# separation.net
KiCad netlist of a schematic drawn in EAGLE
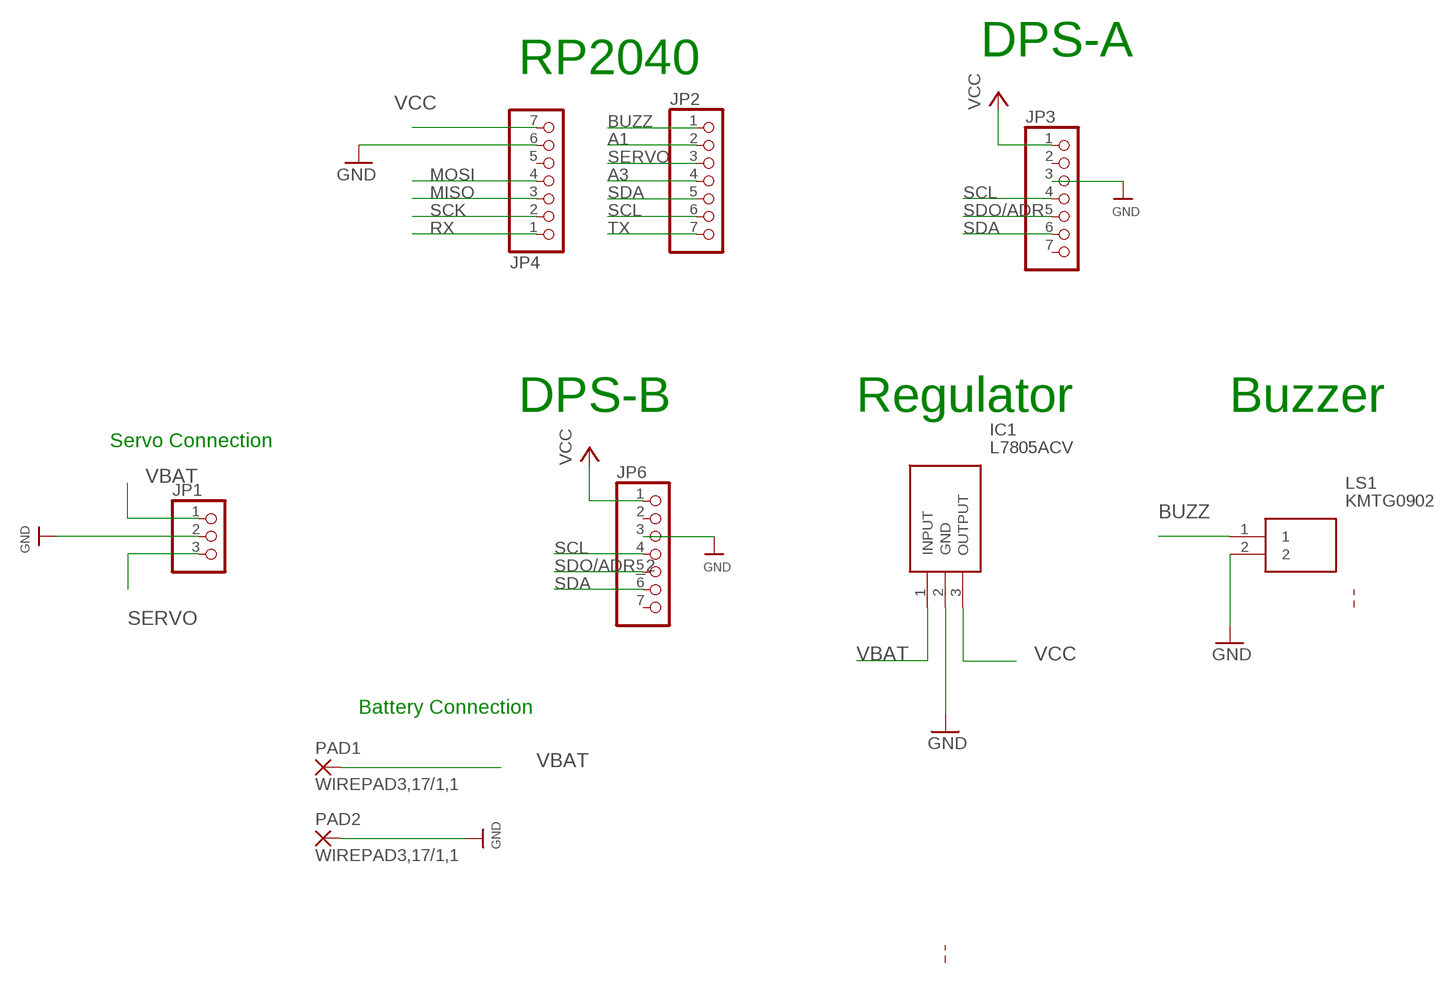
[diagram p0: schematic, sheet 1]

(export (version "E")
  (design (tool "Eeschema 10.0.6"))
  (components
    (comp (ref "IC1")
      (value "L7805ACV")
      (footprint "eagle-import:TO255P460X1020X2008-3P")
      (fields (field (name "RS_PART_NUMBER") "2988508P"))
      (libsource (lib "eagle-import") (part "L7805ACV"))
    )
    (comp (ref "JP1")
      (value "PINHD-1X3")
      (footprint "eagle-import:1X03")
      (libsource (lib "eagle-import") (part "PINHD-1X3"))
    )
    (comp (ref "JP2")
      (value "HEADER-1X7")
      (footprint "eagle-import:1X07_OVAL")
      (libsource (lib "eagle-import") (part "HEADER-1X7"))
    )
    (comp (ref "JP3")
      (value "HEADER-1X770MIL")
      (footprint "eagle-import:1X07_ROUND_70")
      (libsource (lib "eagle-import") (part "HEADER-1X770MIL"))
    )
    (comp (ref "JP4")
      (value "HEADER-1X7")
      (footprint "eagle-import:1X07_OVAL")
      (libsource (lib "eagle-import") (part "HEADER-1X7"))
    )
    (comp (ref "JP6")
      (value "HEADER-1X770MIL")
      (footprint "eagle-import:1X07_ROUND_70")
      (libsource (lib "eagle-import") (part "HEADER-1X770MIL"))
    )
    (comp (ref "LS1")
      (value "KMTG0902")
      (footprint "eagle-import:KMTG0902")
      (fields (field (name "RS_PART_NUMBER") "1812715"))
      (libsource (lib "eagle-import") (part "KMTG0902"))
    )
    (comp (ref "PAD1")
      (value "WIREPAD3,17/1,1")
      (footprint "eagle-import:3,17_1,1")
      (libsource (lib "eagle-import") (part "WIREPAD3,17/1,1"))
    )
    (comp (ref "PAD2")
      (value "WIREPAD3,17/1,1")
      (footprint "eagle-import:3,17_1,1")
      (libsource (lib "eagle-import") (part "WIREPAD3,17/1,1"))
    )
  )
  (nets
    (net (code "1") (name "/A1") (class "Default")
      (node (ref "JP2") (pin "2") (pinfunction "2_2") (pintype "passive"))
    )
    (net (code "2") (name "/A3") (class "Default")
      (node (ref "JP2") (pin "4") (pinfunction "4_4") (pintype "passive"))
    )
    (net (code "3") (name "/BUZZ") (class "Default")
      (node (ref "JP2") (pin "1") (pinfunction "1_1") (pintype "passive"))
      (node (ref "LS1") (pin "1") (pinfunction "1_1") (pintype "bidirectional"))
    )
    (net (code "4") (name "/MISO") (class "Default")
      (node (ref "JP4") (pin "3") (pinfunction "3_3") (pintype "passive"))
    )
    (net (code "5") (name "/MOSI") (class "Default")
      (node (ref "JP4") (pin "4") (pinfunction "4_4") (pintype "passive"))
    )
    (net (code "6") (name "/RX") (class "Default")
      (node (ref "JP4") (pin "1") (pinfunction "1_1") (pintype "passive"))
    )
    (net (code "7") (name "/SCK") (class "Default")
      (node (ref "JP4") (pin "2") (pinfunction "2_2") (pintype "passive"))
    )
    (net (code "8") (name "/SCL") (class "Default")
      (node (ref "JP2") (pin "6") (pinfunction "6_6") (pintype "passive"))
      (node (ref "JP3") (pin "4") (pinfunction "4_4") (pintype "passive"))
      (node (ref "JP6") (pin "4") (pinfunction "4_4") (pintype "passive"))
    )
    (net (code "9") (name "/SDA") (class "Default")
      (node (ref "JP2") (pin "5") (pinfunction "5_5") (pintype "passive"))
      (node (ref "JP3") (pin "6") (pinfunction "6_6") (pintype "passive"))
      (node (ref "JP6") (pin "6") (pinfunction "6_6") (pintype "passive"))
    )
    (net (code "10") (name "/SDO{slash}ADR") (class "Default")
      (node (ref "JP3") (pin "5") (pinfunction "5_5") (pintype "passive"))
    )
    (net (code "11") (name "/SDO{slash}ADR_2") (class "Default")
      (node (ref "JP6") (pin "5") (pinfunction "5_5") (pintype "passive"))
    )
    (net (code "12") (name "/SERVO") (class "Default")
      (node (ref "JP1") (pin "3") (pinfunction "3_3") (pintype "passive"))
      (node (ref "JP2") (pin "3") (pinfunction "3_3") (pintype "passive"))
    )
    (net (code "13") (name "/TX") (class "Default")
      (node (ref "JP2") (pin "7") (pinfunction "7_7") (pintype "passive"))
    )
    (net (code "14") (name "/VBAT") (class "Default")
      (node (ref "IC1") (pin "1") (pinfunction "INPUT_1") (pintype "bidirectional"))
      (node (ref "JP1") (pin "1") (pinfunction "1_1") (pintype "passive"))
      (node (ref "PAD1") (pin "1") (pinfunction "P_1") (pintype "passive"))
    )
    (net (code "15") (name "GND") (class "Default")
      (node (ref "IC1") (pin "2") (pinfunction "GND_2") (pintype "bidirectional"))
      (node (ref "JP1") (pin "2") (pinfunction "2_2") (pintype "passive"))
      (node (ref "JP3") (pin "3") (pinfunction "3_3") (pintype "passive"))
      (node (ref "JP4") (pin "6") (pinfunction "6_6") (pintype "passive"))
      (node (ref "JP6") (pin "3") (pinfunction "3_3") (pintype "passive"))
      (node (ref "LS1") (pin "2") (pinfunction "2_2") (pintype "bidirectional"))
      (node (ref "PAD2") (pin "1") (pinfunction "P_1") (pintype "passive"))
    )
    (net (code "16") (name "VCC") (class "Default")
      (node (ref "IC1") (pin "3") (pinfunction "OUTPUT_3") (pintype "bidirectional"))
      (node (ref "JP3") (pin "1") (pinfunction "1_1") (pintype "passive"))
      (node (ref "JP4") (pin "7") (pinfunction "7_7") (pintype "passive"))
      (node (ref "JP6") (pin "1") (pinfunction "1_1") (pintype "passive"))
    )
    (net (code "17") (name "unconnected-(JP3-Pad2)") (class "Default")
      (node (ref "JP3") (pin "2") (pinfunction "2_2") (pintype "passive"))
    )
    (net (code "18") (name "unconnected-(JP3-Pad7)") (class "Default")
      (node (ref "JP3") (pin "7") (pinfunction "7_7") (pintype "passive"))
    )
    (net (code "19") (name "unconnected-(JP4-Pad5)") (class "Default")
      (node (ref "JP4") (pin "5") (pinfunction "5_5") (pintype "passive"))
    )
    (net (code "20") (name "unconnected-(JP6-Pad2)") (class "Default")
      (node (ref "JP6") (pin "2") (pinfunction "2_2") (pintype "passive"))
    )
    (net (code "21") (name "unconnected-(JP6-Pad7)") (class "Default")
      (node (ref "JP6") (pin "7") (pinfunction "7_7") (pintype "passive"))
    )
  )
)
